# board.net
KiCad netlist of a schematic drawn in EAGLE
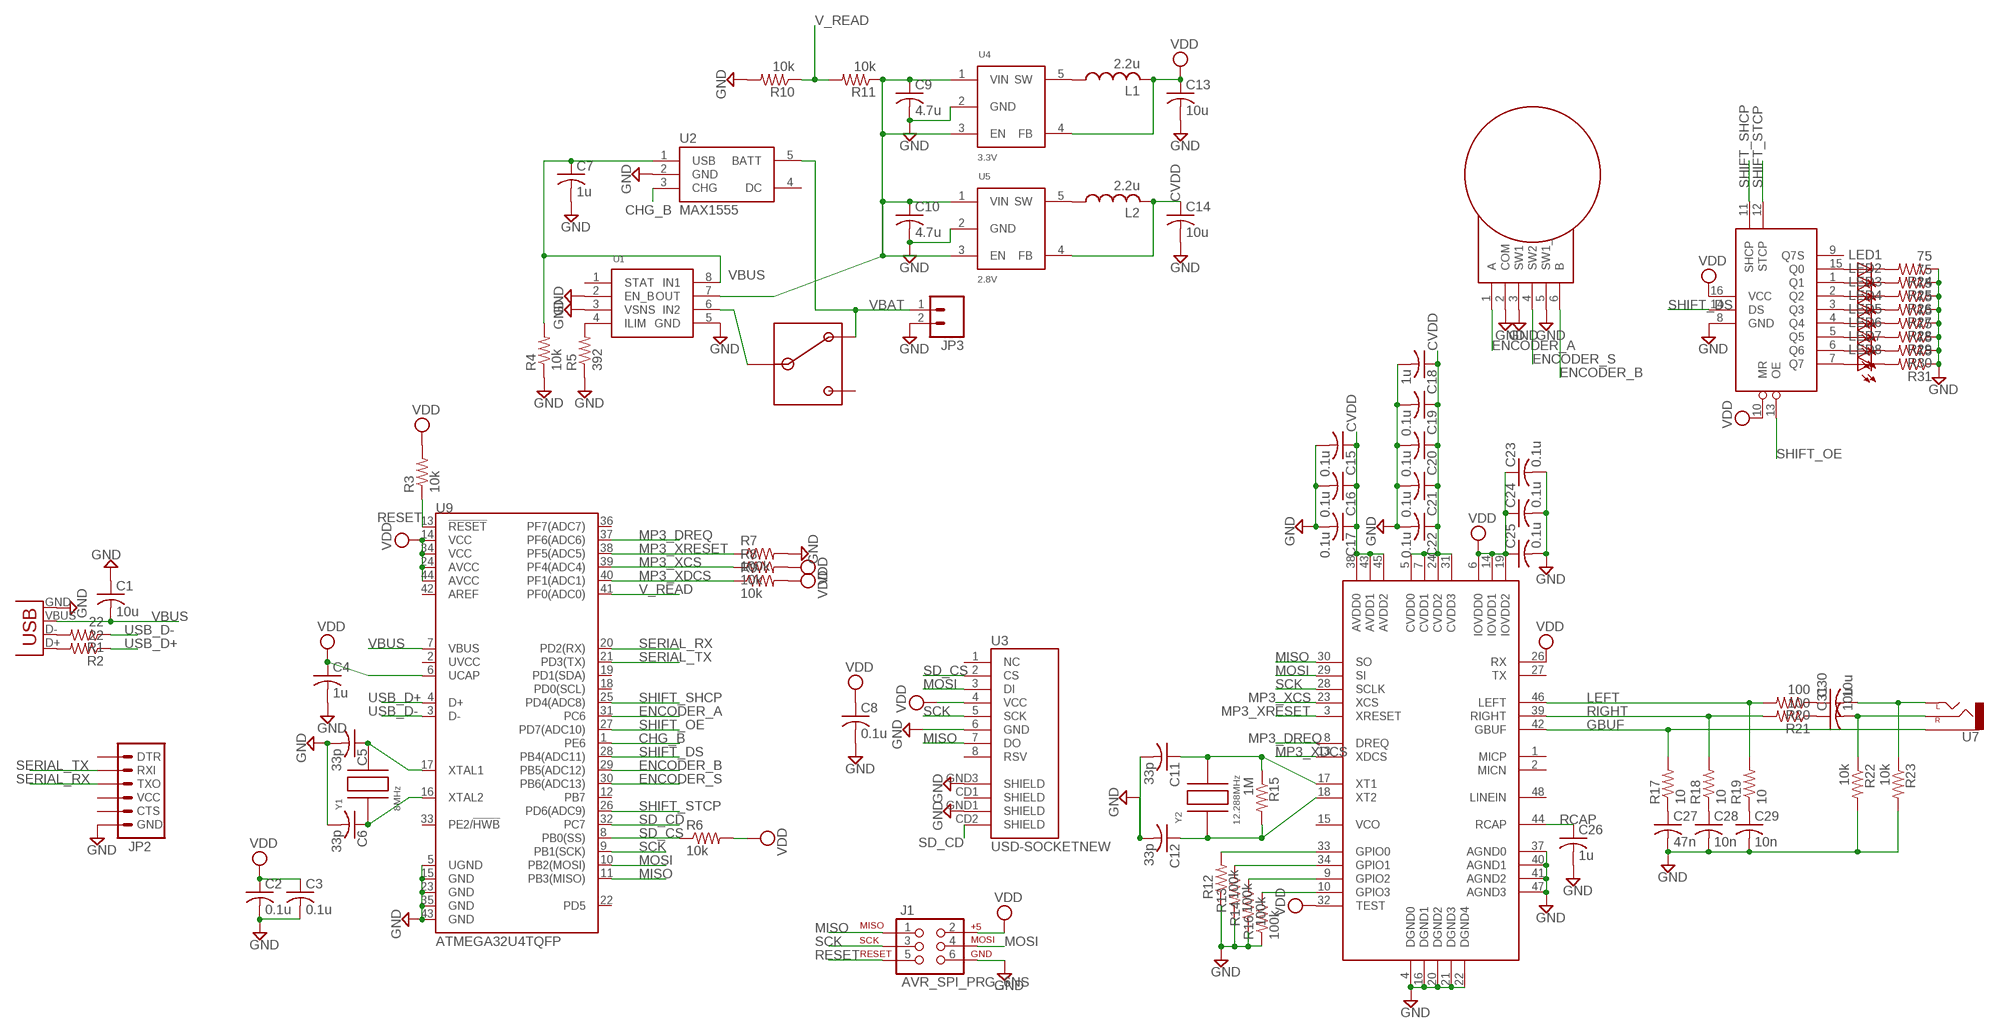
[diagram p0: schematic, sheet 1]

(export (version "E")
  (design (tool "Eeschema 10.0.6"))
  (components
    (comp (ref "C1")
      (value "10u")
      (footprint "eagle-import:C0603K")
      (libsource (lib "eagle-import") (part "C-USC0603K"))
    )
    (comp (ref "C2")
      (value "0.1u")
      (footprint "eagle-import:C0603K")
      (libsource (lib "eagle-import") (part "C-USC0603K"))
    )
    (comp (ref "C3")
      (value "0.1u")
      (footprint "eagle-import:C0603K")
      (libsource (lib "eagle-import") (part "C-USC0603K"))
    )
    (comp (ref "C4")
      (value "1u")
      (footprint "eagle-import:C0603K")
      (libsource (lib "eagle-import") (part "C-USC0603K"))
    )
    (comp (ref "C5")
      (value "33p")
      (footprint "eagle-import:C0603K")
      (libsource (lib "eagle-import") (part "C-USC0603K"))
    )
    (comp (ref "C6")
      (value "33p")
      (footprint "eagle-import:C0603K")
      (libsource (lib "eagle-import") (part "C-USC0603K"))
    )
    (comp (ref "C7")
      (value "1u")
      (footprint "eagle-import:C0603K")
      (libsource (lib "eagle-import") (part "C-USC0603K"))
    )
    (comp (ref "C8")
      (value "0.1u")
      (footprint "eagle-import:C0603K")
      (libsource (lib "eagle-import") (part "C-USC0603K"))
    )
    (comp (ref "C9")
      (value "4.7u")
      (footprint "eagle-import:C0603K")
      (libsource (lib "eagle-import") (part "C-USC0603K"))
    )
    (comp (ref "C10")
      (value "4.7u")
      (footprint "eagle-import:C0603K")
      (libsource (lib "eagle-import") (part "C-USC0603K"))
    )
    (comp (ref "C11")
      (value "33p")
      (footprint "eagle-import:C0603K")
      (libsource (lib "eagle-import") (part "C-USC0603K"))
    )
    (comp (ref "C12")
      (value "33p")
      (footprint "eagle-import:C0603K")
      (libsource (lib "eagle-import") (part "C-USC0603K"))
    )
    (comp (ref "C13")
      (value "10u")
      (footprint "eagle-import:C0603K")
      (libsource (lib "eagle-import") (part "C-USC0603K"))
    )
    (comp (ref "C14")
      (value "10u")
      (footprint "eagle-import:C0603K")
      (libsource (lib "eagle-import") (part "C-USC0603K"))
    )
    (comp (ref "C15")
      (value "0.1u")
      (footprint "eagle-import:C0603K")
      (libsource (lib "eagle-import") (part "C-USC0603K"))
    )
    (comp (ref "C16")
      (value "0.1u")
      (footprint "eagle-import:C0603K")
      (libsource (lib "eagle-import") (part "C-USC0603K"))
    )
    (comp (ref "C17")
      (value "0.1u")
      (footprint "eagle-import:C0603K")
      (libsource (lib "eagle-import") (part "C-USC0603K"))
    )
    (comp (ref "C18")
      (value "1u")
      (footprint "eagle-import:C0603K")
      (libsource (lib "eagle-import") (part "C-USC0603K"))
    )
    (comp (ref "C19")
      (value "0.1u")
      (footprint "eagle-import:C0603K")
      (libsource (lib "eagle-import") (part "C-USC0603K"))
    )
    (comp (ref "C20")
      (value "0.1u")
      (footprint "eagle-import:C0603K")
      (libsource (lib "eagle-import") (part "C-USC0603K"))
    )
    (comp (ref "C21")
      (value "0.1u")
      (footprint "eagle-import:C0603K")
      (libsource (lib "eagle-import") (part "C-USC0603K"))
    )
    (comp (ref "C22")
      (value "0.1u")
      (footprint "eagle-import:C0603K")
      (libsource (lib "eagle-import") (part "C-USC0603K"))
    )
    (comp (ref "C23")
      (value "0.1u")
      (footprint "eagle-import:C0603K")
      (libsource (lib "eagle-import") (part "C-USC0603K"))
    )
    (comp (ref "C24")
      (value "0.1u")
      (footprint "eagle-import:C0603K")
      (libsource (lib "eagle-import") (part "C-USC0603K"))
    )
    (comp (ref "C25")
      (value "0.1u")
      (footprint "eagle-import:C0603K")
      (libsource (lib "eagle-import") (part "C-USC0603K"))
    )
    (comp (ref "C26")
      (value "1u")
      (footprint "eagle-import:C0603K")
      (libsource (lib "eagle-import") (part "C-USC0603K"))
    )
    (comp (ref "C27")
      (value "47n")
      (footprint "eagle-import:C0603K")
      (libsource (lib "eagle-import") (part "C-USC0603K"))
    )
    (comp (ref "C28")
      (value "10n")
      (footprint "eagle-import:C0603K")
      (libsource (lib "eagle-import") (part "C-USC0603K"))
    )
    (comp (ref "C29")
      (value "10n")
      (footprint "eagle-import:C0603K")
      (libsource (lib "eagle-import") (part "C-USC0603K"))
    )
    (comp (ref "C30")
      (value "10u")
      (footprint "eagle-import:C0603K")
      (libsource (lib "eagle-import") (part "C-USC0603K"))
    )
    (comp (ref "C31")
      (value "10u")
      (footprint "eagle-import:C0603K")
      (libsource (lib "eagle-import") (part "C-USC0603K"))
    )
    (comp (ref "J1")
      (value "AVR_SPI_PRG_6NS")
      (footprint "eagle-import:2X3-NS")
      (libsource (lib "eagle-import") (part "AVR_SPI_PRG_6NS"))
    )
    (comp (ref "JP1")
      (value "USBSMD")
      (footprint "eagle-import:USB-MINIB")
      (libsource (lib "eagle-import") (part "USBSMD"))
    )
    (comp (ref "JP2")
      (value "ARDUINO_SERIAL_PROGRAMLOCK")
      (footprint "eagle-import:1X06_LOCK")
      (libsource (lib "eagle-import") (part "ARDUINO_SERIAL_PROGRAMLOCK"))
    )
    (comp (ref "JP3")
      (value "M02PTH")
      (footprint "eagle-import:1X02")
      (libsource (lib "eagle-import") (part "M02PTH"))
    )
    (comp (ref "L1")
      (value "2.2u")
      (footprint "eagle-import:IHLP-2020CZ-11")
      (libsource (lib "eagle-import") (part "IHLP-2020CZ-11"))
    )
    (comp (ref "L2")
      (value "2.2u")
      (footprint "eagle-import:IHLP-2020CZ-11")
      (libsource (lib "eagle-import") (part "IHLP-2020CZ-11"))
    )
    (comp (ref "LED1")
      (value "LED1206")
      (footprint "eagle-import:LED-1206")
      (libsource (lib "eagle-import") (part "LED1206"))
    )
    (comp (ref "LED2")
      (value "LED1206")
      (footprint "eagle-import:LED-1206")
      (libsource (lib "eagle-import") (part "LED1206"))
    )
    (comp (ref "LED3")
      (value "LED1206")
      (footprint "eagle-import:LED-1206")
      (libsource (lib "eagle-import") (part "LED1206"))
    )
    (comp (ref "LED4")
      (value "LED1206")
      (footprint "eagle-import:LED-1206")
      (libsource (lib "eagle-import") (part "LED1206"))
    )
    (comp (ref "LED5")
      (value "LED1206")
      (footprint "eagle-import:LED-1206")
      (libsource (lib "eagle-import") (part "LED1206"))
    )
    (comp (ref "LED6")
      (value "LED1206")
      (footprint "eagle-import:LED-1206")
      (libsource (lib "eagle-import") (part "LED1206"))
    )
    (comp (ref "LED7")
      (value "LED1206")
      (footprint "eagle-import:LED-1206")
      (libsource (lib "eagle-import") (part "LED1206"))
    )
    (comp (ref "LED8")
      (value "LED1206")
      (footprint "eagle-import:LED-1206")
      (libsource (lib "eagle-import") (part "LED1206"))
    )
    (comp (ref "R1")
      (value "22")
      (footprint "eagle-import:R0603W")
      (libsource (lib "eagle-import") (part "R-US_R0603W"))
    )
    (comp (ref "R2")
      (value "22")
      (footprint "eagle-import:R0603W")
      (libsource (lib "eagle-import") (part "R-US_R0603W"))
    )
    (comp (ref "R3")
      (value "10k")
      (footprint "eagle-import:R0603")
      (libsource (lib "eagle-import") (part "R-US_R0603"))
    )
    (comp (ref "R4")
      (value "10k")
      (footprint "eagle-import:R0603")
      (libsource (lib "eagle-import") (part "R-US_R0603"))
    )
    (comp (ref "R5")
      (value "392")
      (footprint "eagle-import:R0603")
      (libsource (lib "eagle-import") (part "R-US_R0603"))
    )
    (comp (ref "R6")
      (value "10k")
      (footprint "eagle-import:R0603W")
      (libsource (lib "eagle-import") (part "R-US_R0603W"))
    )
    (comp (ref "R7")
      (value "100k")
      (footprint "eagle-import:R0603W")
      (libsource (lib "eagle-import") (part "R-US_R0603W"))
    )
    (comp (ref "R8")
      (value "10k")
      (footprint "eagle-import:R0603W")
      (libsource (lib "eagle-import") (part "R-US_R0603W"))
    )
    (comp (ref "R9")
      (value "10k")
      (footprint "eagle-import:R0603W")
      (libsource (lib "eagle-import") (part "R-US_R0603W"))
    )
    (comp (ref "R10")
      (value "10k")
      (footprint "eagle-import:R0603")
      (libsource (lib "eagle-import") (part "R-US_R0603"))
    )
    (comp (ref "R11")
      (value "10k")
      (footprint "eagle-import:R0603")
      (libsource (lib "eagle-import") (part "R-US_R0603"))
    )
    (comp (ref "R12")
      (value "100k")
      (footprint "eagle-import:R0603W")
      (libsource (lib "eagle-import") (part "R-US_R0603W"))
    )
    (comp (ref "R13")
      (value "100k")
      (footprint "eagle-import:R0603W")
      (libsource (lib "eagle-import") (part "R-US_R0603W"))
    )
    (comp (ref "R14")
      (value "100k")
      (footprint "eagle-import:R0603W")
      (libsource (lib "eagle-import") (part "R-US_R0603W"))
    )
    (comp (ref "R15")
      (value "1M")
      (footprint "eagle-import:R0603")
      (libsource (lib "eagle-import") (part "R-US_R0603"))
    )
    (comp (ref "R16")
      (value "100k")
      (footprint "eagle-import:R0603W")
      (libsource (lib "eagle-import") (part "R-US_R0603W"))
    )
    (comp (ref "R17")
      (value "10")
      (footprint "eagle-import:R0603W")
      (libsource (lib "eagle-import") (part "R-US_R0603W"))
    )
    (comp (ref "R18")
      (value "10")
      (footprint "eagle-import:R0603W")
      (libsource (lib "eagle-import") (part "R-US_R0603W"))
    )
    (comp (ref "R19")
      (value "10")
      (footprint "eagle-import:R0603W")
      (libsource (lib "eagle-import") (part "R-US_R0603W"))
    )
    (comp (ref "R20")
      (value "100")
      (footprint "eagle-import:R0603W")
      (libsource (lib "eagle-import") (part "R-US_R0603W"))
    )
    (comp (ref "R21")
      (value "100")
      (footprint "eagle-import:R0603W")
      (libsource (lib "eagle-import") (part "R-US_R0603W"))
    )
    (comp (ref "R22")
      (value "10k")
      (footprint "eagle-import:R0603W")
      (libsource (lib "eagle-import") (part "R-US_R0603W"))
    )
    (comp (ref "R23")
      (value "10k")
      (footprint "eagle-import:R0603W")
      (libsource (lib "eagle-import") (part "R-US_R0603W"))
    )
    (comp (ref "R24")
      (value "75")
      (footprint "eagle-import:R0603W")
      (libsource (lib "eagle-import") (part "R-US_R0603W"))
    )
    (comp (ref "R25")
      (value "75")
      (footprint "eagle-import:R0603W")
      (libsource (lib "eagle-import") (part "R-US_R0603W"))
    )
    (comp (ref "R26")
      (value "75")
      (footprint "eagle-import:R0603W")
      (libsource (lib "eagle-import") (part "R-US_R0603W"))
    )
    (comp (ref "R27")
      (value "75")
      (footprint "eagle-import:R0603W")
      (libsource (lib "eagle-import") (part "R-US_R0603W"))
    )
    (comp (ref "R28")
      (value "75")
      (footprint "eagle-import:R0603W")
      (libsource (lib "eagle-import") (part "R-US_R0603W"))
    )
    (comp (ref "R29")
      (value "75")
      (footprint "eagle-import:R0603W")
      (libsource (lib "eagle-import") (part "R-US_R0603W"))
    )
    (comp (ref "R30")
      (value "75")
      (footprint "eagle-import:R0603W")
      (libsource (lib "eagle-import") (part "R-US_R0603W"))
    )
    (comp (ref "R31")
      (value "75")
      (footprint "eagle-import:R0603W")
      (libsource (lib "eagle-import") (part "R-US_R0603W"))
    )
    (comp (ref "S1")
      (value "JS102011SAQN")
      (footprint "eagle-import:JS102011SAQN")
      (libsource (lib "eagle-import") (part "JS102011SAQN"))
    )
    (comp (ref "S2")
      (value "EVQ-WKA")
      (footprint "eagle-import:EVQ-WKA")
      (libsource (lib "eagle-import") (part "EVQ-WKA"))
    )
    (comp (ref "U1")
      (value "TPS2112A")
      (footprint "eagle-import:TSSOP8")
      (libsource (lib "eagle-import") (part "TPS2112A"))
    )
    (comp (ref "U2")
      (value "MAX1555")
      (footprint "eagle-import:SOT23-5")
      (libsource (lib "eagle-import") (part "MAX1555"))
    )
    (comp (ref "U3")
      (value "USD-SOCKETNEW")
      (footprint "eagle-import:MICRO-SD-SOCKET-PP")
      (libsource (lib "eagle-import") (part "USD-SOCKETNEW"))
    )
    (comp (ref "U4")
      (value "3.3V")
      (footprint "eagle-import:SOT23-5")
      (libsource (lib "eagle-import") (part "LM3671"))
    )
    (comp (ref "U5")
      (value "2.8V")
      (footprint "eagle-import:SOT23-5")
      (libsource (lib "eagle-import") (part "LM3671"))
    )
    (comp (ref "U6")
      (value "74HC595")
      (footprint "eagle-import:TSSOP16")
      (libsource (lib "eagle-import") (part "74HC595"))
    )
    (comp (ref "U7")
      (value "AUDIO-JACKSMD2")
      (footprint "eagle-import:AUDIO-JACK-3.5MM-SMD")
      (libsource (lib "eagle-import") (part "AUDIO-JACKSMD2"))
    )
    (comp (ref "U8")
      (value "VS1003")
      (footprint "eagle-import:LQFP-48")
      (libsource (lib "eagle-import") (part "VS1003"))
    )
    (comp (ref "U9")
      (value "ATMEGA32U4TQFP")
      (footprint "eagle-import:SPARKFUN-DIGITALIC_TQFP44")
      (libsource (lib "eagle-import") (part "ATMEGA32U4TQFP"))
    )
    (comp (ref "Y1")
      (value "8MHz")
      (footprint "eagle-import:HC49_US")
      (libsource (lib "eagle-import") (part "CSM-7X"))
    )
    (comp (ref "Y2")
      (value "12.288MHz")
      (footprint "eagle-import:CSM-3X")
      (libsource (lib "eagle-import") (part "CSM-3X"))
    )
  )
  (nets
    (net (code "1") (name "/CHG_B") (class "Default")
      (node (ref "U2") (pin "3") (pinfunction "CHG_3") (pintype "bidirectional"))
      (node (ref "U9") (pin "1") (pinfunction "PE6_1") (pintype "bidirectional"))
    )
    (net (code "2") (name "/CVDD") (class "Default")
      (node (ref "C14") (pin "1") (pinfunction "1_1") (pintype "passive"))
      (node (ref "C15") (pin "1") (pinfunction "1_1") (pintype "passive"))
      (node (ref "C16") (pin "1") (pinfunction "1_1") (pintype "passive"))
      (node (ref "C17") (pin "1") (pinfunction "1_1") (pintype "passive"))
      (node (ref "C18") (pin "1") (pinfunction "1_1") (pintype "passive"))
      (node (ref "C19") (pin "1") (pinfunction "1_1") (pintype "passive"))
      (node (ref "C20") (pin "1") (pinfunction "1_1") (pintype "passive"))
      (node (ref "C21") (pin "1") (pinfunction "1_1") (pintype "passive"))
      (node (ref "C22") (pin "1") (pinfunction "1_1") (pintype "passive"))
      (node (ref "L2") (pin "P$2") (pinfunction "2_P$2") (pintype "passive"))
      (node (ref "U5") (pin "4") (pinfunction "FB_4") (pintype "bidirectional"))
      (node (ref "U8") (pin "24") (pinfunction "CVDD2_24") (pintype "bidirectional"))
      (node (ref "U8") (pin "31") (pinfunction "CVDD3_31") (pintype "bidirectional"))
      (node (ref "U8") (pin "38") (pinfunction "AVDD0_38") (pintype "bidirectional"))
      (node (ref "U8") (pin "43") (pinfunction "AVDD1_43") (pintype "bidirectional"))
      (node (ref "U8") (pin "45") (pinfunction "AVDD2_45") (pintype "bidirectional"))
      (node (ref "U8") (pin "5") (pinfunction "CVDD0_5") (pintype "bidirectional"))
      (node (ref "U8") (pin "7") (pinfunction "CVDD1_7") (pintype "bidirectional"))
    )
    (net (code "3") (name "/ENCODER_A") (class "Default")
      (node (ref "S2") (pin "1") (pinfunction "A_1") (pintype "bidirectional"))
      (node (ref "U9") (pin "31") (pinfunction "PC6_31") (pintype "bidirectional"))
    )
    (net (code "4") (name "/ENCODER_B") (class "Default")
      (node (ref "S2") (pin "6") (pinfunction "B_6") (pintype "bidirectional"))
      (node (ref "U9") (pin "29") (pinfunction "PB5(ADC12)_29") (pintype "bidirectional"))
    )
    (net (code "5") (name "/ENCODER_S") (class "Default")
      (node (ref "S2") (pin "4") (pinfunction "SW2_4") (pintype "bidirectional"))
      (node (ref "U9") (pin "30") (pinfunction "PB6(ADC13)_30") (pintype "bidirectional"))
    )
    (net (code "6") (name "/GBUF") (class "Default")
      (node (ref "R17") (pin "2") (pinfunction "2_2") (pintype "passive"))
      (node (ref "U7") (pin "SLEEVE") (pinfunction "SLEEVE_SLEEVE") (pintype "bidirectional"))
      (node (ref "U8") (pin "42") (pinfunction "GBUF_42") (pintype "bidirectional"))
    )
    (net (code "7") (name "/LEFT") (class "Default")
      (node (ref "R19") (pin "2") (pinfunction "2_2") (pintype "passive"))
      (node (ref "R20") (pin "2") (pinfunction "2_2") (pintype "passive"))
      (node (ref "U8") (pin "46") (pinfunction "LEFT_46") (pintype "bidirectional"))
    )
    (net (code "8") (name "/MISO") (class "Default")
      (node (ref "J1") (pin "1") (pinfunction "1_1") (pintype "passive"))
      (node (ref "U3") (pin "7") (pinfunction "DO_7") (pintype "bidirectional"))
      (node (ref "U8") (pin "30") (pinfunction "SO_30") (pintype "bidirectional"))
      (node (ref "U9") (pin "11") (pinfunction "PB3(MISO)_11") (pintype "bidirectional"))
    )
    (net (code "9") (name "/MOSI") (class "Default")
      (node (ref "J1") (pin "4") (pinfunction "4_4") (pintype "passive"))
      (node (ref "U3") (pin "3") (pinfunction "DI_3") (pintype "bidirectional"))
      (node (ref "U8") (pin "29") (pinfunction "SI_29") (pintype "bidirectional"))
      (node (ref "U9") (pin "10") (pinfunction "PB2(MOSI)_10") (pintype "bidirectional"))
    )
    (net (code "10") (name "/MP3_DREQ") (class "Default")
      (node (ref "U8") (pin "8") (pinfunction "DREQ_8") (pintype "bidirectional"))
      (node (ref "U9") (pin "37") (pinfunction "PF6(ADC6)_37") (pintype "bidirectional"))
    )
    (net (code "11") (name "/MP3_XCS") (class "Default")
      (node (ref "R8") (pin "1") (pinfunction "1_1") (pintype "passive"))
      (node (ref "U8") (pin "23") (pinfunction "XCS_23") (pintype "bidirectional"))
      (node (ref "U9") (pin "39") (pinfunction "PF4(ADC4)_39") (pintype "bidirectional"))
    )
    (net (code "12") (name "/MP3_XDCS") (class "Default")
      (node (ref "R9") (pin "1") (pinfunction "1_1") (pintype "passive"))
      (node (ref "U8") (pin "13") (pinfunction "XDCS_13") (pintype "bidirectional"))
      (node (ref "U9") (pin "40") (pinfunction "PF1(ADC1)_40") (pintype "bidirectional"))
    )
    (net (code "13") (name "/MP3_XRESET") (class "Default")
      (node (ref "R7") (pin "1") (pinfunction "1_1") (pintype "passive"))
      (node (ref "U8") (pin "3") (pinfunction "XRESET_3") (pintype "bidirectional"))
      (node (ref "U9") (pin "38") (pinfunction "PF5(ADC5)_38") (pintype "bidirectional"))
    )
    (net (code "14") (name "/RCAP") (class "Default")
      (node (ref "C26") (pin "1") (pinfunction "1_1") (pintype "passive"))
      (node (ref "U8") (pin "44") (pinfunction "RCAP_44") (pintype "bidirectional"))
    )
    (net (code "15") (name "/RESET") (class "Default")
      (node (ref "J1") (pin "5") (pinfunction "5_5") (pintype "passive"))
      (node (ref "R3") (pin "1") (pinfunction "1_1") (pintype "passive"))
      (node (ref "U9") (pin "13") (pinfunction "~{RESET}_13") (pintype "bidirectional"))
    )
    (net (code "16") (name "/RIGHT") (class "Default")
      (node (ref "R18") (pin "2") (pinfunction "2_2") (pintype "passive"))
      (node (ref "R21") (pin "2") (pinfunction "2_2") (pintype "passive"))
      (node (ref "U8") (pin "39") (pinfunction "RIGHT_39") (pintype "bidirectional"))
    )
    (net (code "17") (name "/SCK") (class "Default")
      (node (ref "J1") (pin "3") (pinfunction "3_3") (pintype "passive"))
      (node (ref "U3") (pin "5") (pinfunction "SCK_5") (pintype "bidirectional"))
      (node (ref "U8") (pin "28") (pinfunction "SCLK_28") (pintype "bidirectional"))
      (node (ref "U9") (pin "9") (pinfunction "PB1(SCK)_9") (pintype "bidirectional"))
    )
    (net (code "18") (name "/SD_CD") (class "Default")
      (node (ref "U3") (pin "CD2") (pinfunction "SHIELD_CD2") (pintype "bidirectional"))
      (node (ref "U9") (pin "32") (pinfunction "PC7_32") (pintype "bidirectional"))
    )
    (net (code "19") (name "/SD_CS") (class "Default")
      (node (ref "R6") (pin "1") (pinfunction "1_1") (pintype "passive"))
      (node (ref "U3") (pin "2") (pinfunction "CS_2") (pintype "bidirectional"))
      (node (ref "U9") (pin "8") (pinfunction "PB0(SS)_8") (pintype "bidirectional"))
    )
    (net (code "20") (name "/SERIAL_RX") (class "Default")
      (node (ref "JP2") (pin "3") (pinfunction "TXO_3") (pintype "passive"))
      (node (ref "U9") (pin "20") (pinfunction "PD2(RX)_20") (pintype "bidirectional"))
    )
    (net (code "21") (name "/SERIAL_TX") (class "Default")
      (node (ref "JP2") (pin "2") (pinfunction "RXI_2") (pintype "passive"))
      (node (ref "U9") (pin "21") (pinfunction "PD3(TX)_21") (pintype "bidirectional"))
    )
    (net (code "22") (name "/SHIFT_DS") (class "Default")
      (node (ref "U6") (pin "14") (pinfunction "DS_14") (pintype "bidirectional"))
      (node (ref "U9") (pin "28") (pinfunction "PB4(ADC11)_28") (pintype "bidirectional"))
    )
    (net (code "23") (name "/SHIFT_OE") (class "Default")
      (node (ref "U6") (pin "13") (pinfunction "OE_13") (pintype "bidirectional"))
      (node (ref "U9") (pin "27") (pinfunction "PD7(ADC10)_27") (pintype "bidirectional"))
    )
    (net (code "24") (name "/SHIFT_SHCP") (class "Default")
      (node (ref "U6") (pin "11") (pinfunction "SHCP_11") (pintype "bidirectional"))
      (node (ref "U9") (pin "25") (pinfunction "PD4(ADC8)_25") (pintype "bidirectional"))
    )
    (net (code "25") (name "/SHIFT_STCP") (class "Default")
      (node (ref "U6") (pin "12") (pinfunction "STCP_12") (pintype "bidirectional"))
      (node (ref "U9") (pin "26") (pinfunction "PD6(ADC9)_26") (pintype "bidirectional"))
    )
    (net (code "26") (name "/USB_D+") (class "Default")
      (node (ref "R2") (pin "1") (pinfunction "1_1") (pintype "passive"))
      (node (ref "U9") (pin "4") (pinfunction "D+_4") (pintype "bidirectional"))
    )
    (net (code "27") (name "/USB_D-") (class "Default")
      (node (ref "R1") (pin "1") (pinfunction "1_1") (pintype "passive"))
      (node (ref "U9") (pin "3") (pinfunction "D-_3") (pintype "bidirectional"))
    )
    (net (code "28") (name "/VBAT") (class "Default")
      (node (ref "JP3") (pin "1") (pinfunction "1_1") (pintype "passive"))
      (node (ref "S1") (pin "P$3") (pinfunction "3_P$3") (pintype "bidirectional"))
      (node (ref "U2") (pin "5") (pinfunction "BATT_5") (pintype "bidirectional"))
    )
    (net (code "29") (name "/VBUS") (class "Default")
      (node (ref "C1") (pin "2") (pinfunction "2_2") (pintype "passive"))
      (node (ref "C7") (pin "1") (pinfunction "1_1") (pintype "passive"))
      (node (ref "JP1") (pin "VBUS") (pinfunction "VBUS_VBUS") (pintype "bidirectional"))
      (node (ref "R4") (pin "2") (pinfunction "2_2") (pintype "passive"))
      (node (ref "U1") (pin "8") (pinfunction "IN1_8") (pintype "bidirectional"))
      (node (ref "U2") (pin "1") (pinfunction "USB_1") (pintype "bidirectional"))
      (node (ref "U9") (pin "7") (pinfunction "VBUS_7") (pintype "bidirectional"))
    )
    (net (code "30") (name "/V_READ") (class "Default")
      (node (ref "R10") (pin "1") (pinfunction "1_1") (pintype "passive"))
      (node (ref "R11") (pin "2") (pinfunction "2_2") (pintype "passive"))
      (node (ref "U9") (pin "41") (pinfunction "PF0(ADC0)_41") (pintype "bidirectional"))
    )
    (net (code "31") (name "GND") (class "Default")
      (node (ref "C1") (pin "1") (pinfunction "1_1") (pintype "passive"))
      (node (ref "C10") (pin "2") (pinfunction "2_2") (pintype "passive"))
      (node (ref "C11") (pin "2") (pinfunction "2_2") (pintype "passive"))
      (node (ref "C12") (pin "2") (pinfunction "2_2") (pintype "passive"))
      (node (ref "C13") (pin "2") (pinfunction "2_2") (pintype "passive"))
      (node (ref "C14") (pin "2") (pinfunction "2_2") (pintype "passive"))
      (node (ref "C15") (pin "2") (pinfunction "2_2") (pintype "passive"))
      (node (ref "C16") (pin "2") (pinfunction "2_2") (pintype "passive"))
      (node (ref "C17") (pin "2") (pinfunction "2_2") (pintype "passive"))
      (node (ref "C18") (pin "2") (pinfunction "2_2") (pintype "passive"))
      (node (ref "C19") (pin "2") (pinfunction "2_2") (pintype "passive"))
      (node (ref "C2") (pin "2") (pinfunction "2_2") (pintype "passive"))
      (node (ref "C20") (pin "2") (pinfunction "2_2") (pintype "passive"))
      (node (ref "C21") (pin "2") (pinfunction "2_2") (pintype "passive"))
      (node (ref "C22") (pin "2") (pinfunction "2_2") (pintype "passive"))
      (node (ref "C23") (pin "2") (pinfunction "2_2") (pintype "passive"))
      (node (ref "C24") (pin "2") (pinfunction "2_2") (pintype "passive"))
      (node (ref "C25") (pin "2") (pinfunction "2_2") (pintype "passive"))
      (node (ref "C26") (pin "2") (pinfunction "2_2") (pintype "passive"))
      (node (ref "C27") (pin "2") (pinfunction "2_2") (pintype "passive"))
      (node (ref "C28") (pin "2") (pinfunction "2_2") (pintype "passive"))
      (node (ref "C29") (pin "2") (pinfunction "2_2") (pintype "passive"))
      (node (ref "C3") (pin "2") (pinfunction "2_2") (pintype "passive"))
      (node (ref "C4") (pin "2") (pinfunction "2_2") (pintype "passive"))
      (node (ref "C5") (pin "2") (pinfunction "2_2") (pintype "passive"))
      (node (ref "C6") (pin "2") (pinfunction "2_2") (pintype "passive"))
      (node (ref "C7") (pin "2") (pinfunction "2_2") (pintype "passive"))
      (node (ref "C8") (pin "2") (pinfunction "2_2") (pintype "passive"))
      (node (ref "C9") (pin "2") (pinfunction "2_2") (pintype "passive"))
      (node (ref "J1") (pin "6") (pinfunction "6_6") (pintype "passive"))
      (node (ref "JP1") (pin "GND") (pinfunction "GND_GND") (pintype "bidirectional"))
      (node (ref "JP2") (pin "6") (pinfunction "GND_6") (pintype "passive"))
      (node (ref "JP3") (pin "2") (pinfunction "2_2") (pintype "passive"))
      (node (ref "R10") (pin "2") (pinfunction "2_2") (pintype "passive"))
      (node (ref "R12") (pin "1") (pinfunction "1_1") (pintype "passive"))
      (node (ref "R13") (pin "1") (pinfunction "1_1") (pintype "passive"))
      (node (ref "R14") (pin "1") (pinfunction "1_1") (pintype "passive"))
      (node (ref "R16") (pin "1") (pinfunction "1_1") (pintype "passive"))
      (node (ref "R22") (pin "2") (pinfunction "2_2") (pintype "passive"))
      (node (ref "R23") (pin "2") (pinfunction "2_2") (pintype "passive"))
      (node (ref "R24") (pin "1") (pinfunction "1_1") (pintype "passive"))
      (node (ref "R25") (pin "1") (pinfunction "1_1") (pintype "passive"))
      (node (ref "R26") (pin "1") (pinfunction "1_1") (pintype "passive"))
      (node (ref "R27") (pin "1") (pinfunction "1_1") (pintype "passive"))
      (node (ref "R28") (pin "1") (pinfunction "1_1") (pintype "passive"))
      (node (ref "R29") (pin "1") (pinfunction "1_1") (pintype "passive"))
      (node (ref "R30") (pin "1") (pinfunction "1_1") (pintype "passive"))
      (node (ref "R31") (pin "1") (pinfunction "1_1") (pintype "passive"))
      (node (ref "R4") (pin "1") (pinfunction "1_1") (pintype "passive"))
      (node (ref "R5") (pin "1") (pinfunction "1_1") (pintype "passive"))
      (node (ref "R7") (pin "2") (pinfunction "2_2") (pintype "passive"))
      (node (ref "S2") (pin "2") (pinfunction "COM_2") (pintype "bidirectional"))
      (node (ref "S2") (pin "3") (pinfunction "SW1_3") (pintype "bidirectional"))
      (node (ref "S2") (pin "5") (pinfunction "SW1__5") (pintype "bidirectional"))
      (node (ref "U1") (pin "2") (pinfunction "EN_B_2") (pintype "bidirectional"))
      (node (ref "U1") (pin "3") (pinfunction "VSNS_3") (pintype "bidirectional"))
      (node (ref "U1") (pin "5") (pinfunction "GND_5") (pintype "bidirectional"))
      (node (ref "U2") (pin "2") (pinfunction "GND_2") (pintype "bidirectional"))
      (node (ref "U3") (pin "6") (pinfunction "GND_6") (pintype "bidirectional"))
      (node (ref "U3") (pin "GND1") (pinfunction "SHIELD_GND1") (pintype "bidirectional"))
      (node (ref "U3") (pin "GND3") (pinfunction "SHIELD_GND3") (pintype "bidirectional"))
      (node (ref "U4") (pin "2") (pinfunction "GND_2") (pintype "bidirectional"))
      (node (ref "U5") (pin "2") (pinfunction "GND_2") (pintype "bidirectional"))
      (node (ref "U6") (pin "8") (pinfunction "GND_8") (pintype "bidirectional"))
      (node (ref "U8") (pin "16") (pinfunction "DGND1_16") (pintype "bidirectional"))
      (node (ref "U8") (pin "20") (pinfunction "DGND2_20") (pintype "bidirectional"))
      (node (ref "U8") (pin "21") (pinfunction "DGND3_21") (pintype "bidirectional"))
      (node (ref "U8") (pin "22") (pinfunction "DGND4_22") (pintype "bidirectional"))
      (node (ref "U8") (pin "37") (pinfunction "AGND0_37") (pintype "bidirectional"))
      (node (ref "U8") (pin "4") (pinfunction "DGND0_4") (pintype "bidirectional"))
      (node (ref "U8") (pin "40") (pinfunction "AGND1_40") (pintype "bidirectional"))
      (node (ref "U8") (pin "41") (pinfunction "AGND2_41") (pintype "bidirectional"))
      (node (ref "U8") (pin "47") (pinfunction "AGND3_47") (pintype "bidirectional"))
      (node (ref "U9") (pin "15") (pinfunction "GND_15") (pintype "bidirectional"))
      (node (ref "U9") (pin "23") (pinfunction "GND_23") (pintype "bidirectional"))
      (node (ref "U9") (pin "35") (pinfunction "GND_35") (pintype "bidirectional"))
      (node (ref "U9") (pin "43") (pinfunction "GND_43") (pintype "bidirectional"))
      (node (ref "U9") (pin "5") (pinfunction "UGND_5") (pintype "bidirectional"))
    )
    (net (code "32") (name "Net-(C27-Pad1)") (class "Default")
      (node (ref "C27") (pin "1") (pinfunction "1_1") (pintype "passive"))
      (node (ref "R17") (pin "1") (pinfunction "1_1") (pintype "passive"))
    )
    (net (code "33") (name "Net-(C28-Pad1)") (class "Default")
      (node (ref "C28") (pin "1") (pinfunction "1_1") (pintype "passive"))
      (node (ref "R18") (pin "1") (pinfunction "1_1") (pintype "passive"))
    )
    (net (code "34") (name "Net-(C29-Pad1)") (class "Default")
      (node (ref "C29") (pin "1") (pinfunction "1_1") (pintype "passive"))
      (node (ref "R19") (pin "1") (pinfunction "1_1") (pintype "passive"))
    )
    (net (code "35") (name "Net-(C30-Pad1)") (class "Default")
      (node (ref "C30") (pin "1") (pinfunction "1_1") (pintype "passive"))
      (node (ref "R20") (pin "1") (pinfunction "1_1") (pintype "passive"))
    )
    (net (code "36") (name "Net-(C31-Pad1)") (class "Default")
      (node (ref "C31") (pin "1") (pinfunction "1_1") (pintype "passive"))
      (node (ref "R21") (pin "1") (pinfunction "1_1") (pintype "passive"))
    )
    (net (code "37") (name "Net-(JP1-PadD+)") (class "Default")
      (node (ref "JP1") (pin "D+") (pinfunction "D+_D+") (pintype "bidirectional"))
      (node (ref "R2") (pin "2") (pinfunction "2_2") (pintype "passive"))
    )
    (net (code "38") (name "Net-(JP1-PadD-)") (class "Default")
      (node (ref "JP1") (pin "D-") (pinfunction "D-_D-") (pintype "bidirectional"))
      (node (ref "R1") (pin "2") (pinfunction "2_2") (pintype "passive"))
    )
    (net (code "39") (name "Net-(L1-1)") (class "Default")
      (node (ref "L1") (pin "P$1") (pinfunction "1_P$1") (pintype "passive"))
      (node (ref "U4") (pin "5") (pinfunction "SW_5") (pintype "bidirectional"))
    )
    (net (code "40") (name "Net-(L2-1)") (class "Default")
      (node (ref "L2") (pin "P$1") (pinfunction "1_P$1") (pintype "passive"))
      (node (ref "U5") (pin "5") (pinfunction "SW_5") (pintype "bidirectional"))
    )
    (net (code "41") (name "Net-(LED1-PadC)") (class "Default")
      (node (ref "LED1") (pin "C") (pinfunction "C_C") (pintype "passive"))
      (node (ref "R24") (pin "2") (pinfunction "2_2") (pintype "passive"))
    )
    (net (code "42") (name "Net-(LED2-PadC)") (class "Default")
      (node (ref "LED2") (pin "C") (pinfunction "C_C") (pintype "passive"))
      (node (ref "R25") (pin "2") (pinfunction "2_2") (pintype "passive"))
    )
    (net (code "43") (name "Net-(LED3-PadC)") (class "Default")
      (node (ref "LED3") (pin "C") (pinfunction "C_C") (pintype "passive"))
      (node (ref "R26") (pin "2") (pinfunction "2_2") (pintype "passive"))
    )
    (net (code "44") (name "Net-(LED4-PadC)") (class "Default")
      (node (ref "LED4") (pin "C") (pinfunction "C_C") (pintype "passive"))
      (node (ref "R27") (pin "2") (pinfunction "2_2") (pintype "passive"))
    )
    (net (code "45") (name "Net-(LED5-PadC)") (class "Default")
      (node (ref "LED5") (pin "C") (pinfunction "C_C") (pintype "passive"))
      (node (ref "R28") (pin "2") (pinfunction "2_2") (pintype "passive"))
    )
    (net (code "46") (name "Net-(LED6-PadC)") (class "Default")
      (node (ref "LED6") (pin "C") (pinfunction "C_C") (pintype "passive"))
      (node (ref "R29") (pin "2") (pinfunction "2_2") (pintype "passive"))
    )
    (net (code "47") (name "Net-(LED7-PadC)") (class "Default")
      (node (ref "LED7") (pin "C") (pinfunction "C_C") (pintype "passive"))
      (node (ref "R30") (pin "2") (pinfunction "2_2") (pintype "passive"))
    )
    (net (code "48") (name "Net-(LED8-PadC)") (class "Default")
      (node (ref "LED8") (pin "C") (pinfunction "C_C") (pintype "passive"))
      (node (ref "R31") (pin "2") (pinfunction "2_2") (pintype "passive"))
    )
    (net (code "49") (name "Net-(S1-2)") (class "Default")
      (node (ref "S1") (pin "P$2") (pinfunction "2_P$2") (pintype "bidirectional"))
      (node (ref "U1") (pin "6") (pinfunction "IN2_6") (pintype "bidirectional"))
    )
    (net (code "50") (name "Net-(U1-ILIM)") (class "Default")
      (node (ref "R5") (pin "2") (pinfunction "2_2") (pintype "passive"))
      (node (ref "U1") (pin "4") (pinfunction "ILIM_4") (pintype "bidirectional"))
    )
    (net (code "51") (name "Net-(U1-OUT)") (class "Default")
      (node (ref "C10") (pin "1") (pinfunction "1_1") (pintype "passive"))
      (node (ref "C9") (pin "1") (pinfunction "1_1") (pintype "passive"))
      (node (ref "R11") (pin "1") (pinfunction "1_1") (pintype "passive"))
      (node (ref "U1") (pin "7") (pinfunction "OUT_7") (pintype "bidirectional"))
      (node (ref "U4") (pin "1") (pinfunction "VIN_1") (pintype "bidirectional"))
      (node (ref "U4") (pin "3") (pinfunction "EN_3") (pintype "bidirectional"))
      (node (ref "U5") (pin "1") (pinfunction "VIN_1") (pintype "bidirectional"))
      (node (ref "U5") (pin "3") (pinfunction "EN_3") (pintype "bidirectional"))
    )
    (net (code "52") (name "Net-(U6-Q0)") (class "Default")
      (node (ref "LED1") (pin "A") (pinfunction "A_A") (pintype "passive"))
      (node (ref "U6") (pin "15") (pinfunction "Q0_15") (pintype "bidirectional"))
    )
    (net (code "53") (name "Net-(U6-Q1)") (class "Default")
      (node (ref "LED2") (pin "A") (pinfunction "A_A") (pintype "passive"))
      (node (ref "U6") (pin "1") (pinfunction "Q1_1") (pintype "bidirectional"))
    )
    (net (code "54") (name "Net-(U6-Q2)") (class "Default")
      (node (ref "LED3") (pin "A") (pinfunction "A_A") (pintype "passive"))
      (node (ref "U6") (pin "2") (pinfunction "Q2_2") (pintype "bidirectional"))
    )
    (net (code "55") (name "Net-(U6-Q3)") (class "Default")
      (node (ref "LED4") (pin "A") (pinfunction "A_A") (pintype "passive"))
      (node (ref "U6") (pin "3") (pinfunction "Q3_3") (pintype "bidirectional"))
    )
    (net (code "56") (name "Net-(U6-Q4)") (class "Default")
      (node (ref "LED5") (pin "A") (pinfunction "A_A") (pintype "passive"))
      (node (ref "U6") (pin "4") (pinfunction "Q4_4") (pintype "bidirectional"))
    )
    (net (code "57") (name "Net-(U6-Q5)") (class "Default")
      (node (ref "LED6") (pin "A") (pinfunction "A_A") (pintype "passive"))
      (node (ref "U6") (pin "5") (pinfunction "Q5_5") (pintype "bidirectional"))
    )
    (net (code "58") (name "Net-(U6-Q6)") (class "Default")
      (node (ref "LED7") (pin "A") (pinfunction "A_A") (pintype "passive"))
      (node (ref "U6") (pin "6") (pinfunction "Q6_6") (pintype "bidirectional"))
    )
    (net (code "59") (name "Net-(U6-Q7)") (class "Default")
      (node (ref "LED8") (pin "A") (pinfunction "A_A") (pintype "passive"))
      (node (ref "U6") (pin "7") (pinfunction "Q7_7") (pintype "bidirectional"))
    )
    (net (code "60") (name "Net-(U7-LEFT)") (class "Default")
      (node (ref "C30") (pin "2") (pinfunction "2_2") (pintype "passive"))
      (node (ref "R23") (pin "1") (pinfunction "1_1") (pintype "passive"))
      (node (ref "U7") (pin "TIP") (pinfunction "LEFT_TIP") (pintype "bidirectional"))
    )
    (net (code "61") (name "Net-(U7-RIGHT)") (class "Default")
      (node (ref "C31") (pin "2") (pinfunction "2_2") (pintype "passive"))
      (node (ref "R22") (pin "1") (pinfunction "1_1") (pintype "passive"))
      (node (ref "U7") (pin "RING") (pinfunction "RIGHT_RING") (pintype "bidirectional"))
    )
    (net (code "62") (name "Net-(U8-GPIO0)") (class "Default")
      (node (ref "R12") (pin "2") (pinfunction "2_2") (pintype "passive"))
      (node (ref "U8") (pin "33") (pinfunction "GPIO0_33") (pintype "bidirectional"))
    )
    (net (code "63") (name "Net-(U8-GPIO1)") (class "Default")
      (node (ref "R13") (pin "2") (pinfunction "2_2") (pintype "passive"))
      (node (ref "U8") (pin "34") (pinfunction "GPIO1_34") (pintype "bidirectional"))
    )
    (net (code "64") (name "Net-(U8-GPIO2)") (class "Default")
      (node (ref "R14") (pin "2") (pinfunction "2_2") (pintype "passive"))
      (node (ref "U8") (pin "9") (pinfunction "GPIO2_9") (pintype "bidirectional"))
    )
    (net (code "65") (name "Net-(U8-GPIO3)") (class "Default")
      (node (ref "R16") (pin "2") (pinfunction "2_2") (pintype "passive"))
      (node (ref "U8") (pin "10") (pinfunction "GPIO3_10") (pintype "bidirectional"))
    )
    (net (code "66") (name "Net-(U8-XT1)") (class "Default")
      (node (ref "C11") (pin "1") (pinfunction "1_1") (pintype "passive"))
      (node (ref "R15") (pin "1") (pinfunction "1_1") (pintype "passive"))
      (node (ref "U8") (pin "17") (pinfunction "XT1_17") (pintype "bidirectional"))
      (node (ref "Y2") (pin "P$2") (pinfunction "P$2_P$2") (pintype "bidirectional"))
    )
    (net (code "67") (name "Net-(U8-XT2)") (class "Default")
      (node (ref "C12") (pin "1") (pinfunction "1_1") (pintype "passive"))
      (node (ref "R15") (pin "2") (pinfunction "2_2") (pintype "passive"))
      (node (ref "U8") (pin "18") (pinfunction "XT2_18") (pintype "bidirectional"))
      (node (ref "Y2") (pin "P$1") (pinfunction "P$1_P$1") (pintype "bidirectional"))
    )
    (net (code "68") (name "Net-(U9-XTAL1)") (class "Default")
      (node (ref "C5") (pin "1") (pinfunction "1_1") (pintype "passive"))
      (node (ref "U9") (pin "17") (pinfunction "XTAL1_17") (pintype "bidirectional"))
      (node (ref "Y1") (pin "P$2") (pinfunction "P$2_P$2") (pintype "bidirectional"))
    )
    (net (code "69") (name "Net-(U9-XTAL2)") (class "Default")
      (node (ref "C6") (pin "1") (pinfunction "1_1") (pintype "passive"))
      (node (ref "U9") (pin "16") (pinfunction "XTAL2_16") (pintype "bidirectional"))
      (node (ref "Y1") (pin "P$1") (pinfunction "P$1_P$1") (pintype "bidirectional"))
    )
    (net (code "70") (name "VDD") (class "Default")
      (node (ref "C13") (pin "1") (pinfunction "1_1") (pintype "passive"))
      (node (ref "C2") (pin "1") (pinfunction "1_1") (pintype "passive"))
      (node (ref "C23") (pin "1") (pinfunction "1_1") (pintype "passive"))
      (node (ref "C24") (pin "1") (pinfunction "1_1") (pintype "passive"))
      (node (ref "C25") (pin "1") (pinfunction "1_1") (pintype "passive"))
      (node (ref "C3") (pin "1") (pinfunction "1_1") (pintype "passive"))
      (node (ref "C4") (pin "1") (pinfunction "1_1") (pintype "passive"))
      (node (ref "C8") (pin "1") (pinfunction "1_1") (pintype "passive"))
      (node (ref "J1") (pin "2") (pinfunction "2_2") (pintype "passive"))
      (node (ref "L1") (pin "P$2") (pinfunction "2_P$2") (pintype "passive"))
      (node (ref "R3") (pin "2") (pinfunction "2_2") (pintype "passive"))
      (node (ref "R6") (pin "2") (pinfunction "2_2") (pintype "passive"))
      (node (ref "R8") (pin "2") (pinfunction "2_2") (pintype "passive"))
      (node (ref "R9") (pin "2") (pinfunction "2_2") (pintype "passive"))
      (node (ref "U3") (pin "4") (pinfunction "VCC_4") (pintype "bidirectional"))
      (node (ref "U4") (pin "4") (pinfunction "FB_4") (pintype "bidirectional"))
      (node (ref "U6") (pin "10") (pinfunction "MR_10") (pintype "bidirectional"))
      (node (ref "U6") (pin "16") (pinfunction "VCC_16") (pintype "bidirectional"))
      (node (ref "U8") (pin "14") (pinfunction "IOVDD1_14") (pintype "bidirectional"))
      (node (ref "U8") (pin "19") (pinfunction "IOVDD2_19") (pintype "bidirectional"))
      (node (ref "U8") (pin "26") (pinfunction "RX_26") (pintype "bidirectional"))
      (node (ref "U8") (pin "32") (pinfunction "TEST_32") (pintype "bidirectional"))
      (node (ref "U8") (pin "6") (pinfunction "IOVDD0_6") (pintype "bidirectional"))
      (node (ref "U9") (pin "14") (pinfunction "VCC_14") (pintype "bidirectional"))
      (node (ref "U9") (pin "24") (pinfunction "AVCC_24") (pintype "bidirectional"))
      (node (ref "U9") (pin "34") (pinfunction "VCC_34") (pintype "bidirectional"))
      (node (ref "U9") (pin "44") (pinfunction "AVCC_44") (pintype "bidirectional"))
      (node (ref "U9") (pin "6") (pinfunction "UCAP_6") (pintype "bidirectional"))
    )
    (net (code "71") (name "unconnected-(JP2-CTS-Pad5)") (class "Default")
      (node (ref "JP2") (pin "5") (pinfunction "CTS_5") (pintype "passive"))
    )
    (net (code "72") (name "unconnected-(JP2-DTR-Pad1)") (class "Default")
      (node (ref "JP2") (pin "1") (pinfunction "DTR_1") (pintype "passive"))
    )
    (net (code "73") (name "unconnected-(JP2-VCC-Pad4)") (class "Default")
      (node (ref "JP2") (pin "4") (pinfunction "VCC_4") (pintype "passive"))
    )
    (net (code "74") (name "unconnected-(S1-1-PadP$1)") (class "Default")
      (node (ref "S1") (pin "P$1") (pinfunction "1_P$1") (pintype "bidirectional"))
    )
    (net (code "75") (name "unconnected-(U1-STAT-Pad1)") (class "Default")
      (node (ref "U1") (pin "1") (pinfunction "STAT_1") (pintype "bidirectional"))
    )
    (net (code "76") (name "unconnected-(U2-DC-Pad4)") (class "Default")
      (node (ref "U2") (pin "4") (pinfunction "DC_4") (pintype "bidirectional"))
    )
    (net (code "77") (name "unconnected-(U3-NC-Pad1)") (class "Default")
      (node (ref "U3") (pin "1") (pinfunction "NC_1") (pintype "bidirectional"))
    )
    (net (code "78") (name "unconnected-(U3-RSV-Pad8)") (class "Default")
      (node (ref "U3") (pin "8") (pinfunction "RSV_8") (pintype "bidirectional"))
    )
    (net (code "79") (name "unconnected-(U3-SHIELD-PadCD1)") (class "Default")
      (node (ref "U3") (pin "CD1") (pinfunction "SHIELD_CD1") (pintype "bidirectional"))
    )
    (net (code "80") (name "unconnected-(U6-Q7S-Pad9)") (class "Default")
      (node (ref "U6") (pin "9") (pinfunction "Q7S_9") (pintype "bidirectional"))
    )
    (net (code "81") (name "unconnected-(U8-LINEIN-Pad48)") (class "Default")
      (node (ref "U8") (pin "48") (pinfunction "LINEIN_48") (pintype "bidirectional"))
    )
    (net (code "82") (name "unconnected-(U8-MICN-Pad2)") (class "Default")
      (node (ref "U8") (pin "2") (pinfunction "MICN_2") (pintype "bidirectional"))
    )
    (net (code "83") (name "unconnected-(U8-MICP-Pad1)") (class "Default")
      (node (ref "U8") (pin "1") (pinfunction "MICP_1") (pintype "bidirectional"))
    )
    (net (code "84") (name "unconnected-(U8-TX-Pad27)") (class "Default")
      (node (ref "U8") (pin "27") (pinfunction "TX_27") (pintype "bidirectional"))
    )
    (net (code "85") (name "unconnected-(U8-VCO-Pad15)") (class "Default")
      (node (ref "U8") (pin "15") (pinfunction "VCO_15") (pintype "bidirectional"))
    )
    (net (code "86") (name "unconnected-(U9-AREF-Pad42)") (class "Default")
      (node (ref "U9") (pin "42") (pinfunction "AREF_42") (pintype "bidirectional"))
    )
    (net (code "87") (name "unconnected-(U9-PB7-Pad12)") (class "Default")
      (node (ref "U9") (pin "12") (pinfunction "PB7_12") (pintype "bidirectional"))
    )
    (net (code "88") (name "unconnected-(U9-PD0(SCL)-Pad18)") (class "Default")
      (node (ref "U9") (pin "18") (pinfunction "PD0(SCL)_18") (pintype "bidirectional"))
    )
    (net (code "89") (name "unconnected-(U9-PD1(SDA)-Pad19)") (class "Default")
      (node (ref "U9") (pin "19") (pinfunction "PD1(SDA)_19") (pintype "bidirectional"))
    )
    (net (code "90") (name "unconnected-(U9-PD5-Pad22)") (class "Default")
      (node (ref "U9") (pin "22") (pinfunction "PD5_22") (pintype "bidirectional"))
    )
    (net (code "91") (name "unconnected-(U9-PE2{slash}~{HWB}-Pad33)") (class "Default")
      (node (ref "U9") (pin "33") (pinfunction "PE2/~{HWB}_33") (pintype "bidirectional"))
    )
    (net (code "92") (name "unconnected-(U9-PF7(ADC7)-Pad36)") (class "Default")
      (node (ref "U9") (pin "36") (pinfunction "PF7(ADC7)_36") (pintype "bidirectional"))
    )
    (net (code "93") (name "unconnected-(U9-UVCC-Pad2)") (class "Default")
      (node (ref "U9") (pin "2") (pinfunction "UVCC_2") (pintype "bidirectional"))
    )
  )
)
